# Control_Board.net
KiCad netlist of a schematic drawn in Altium Designer
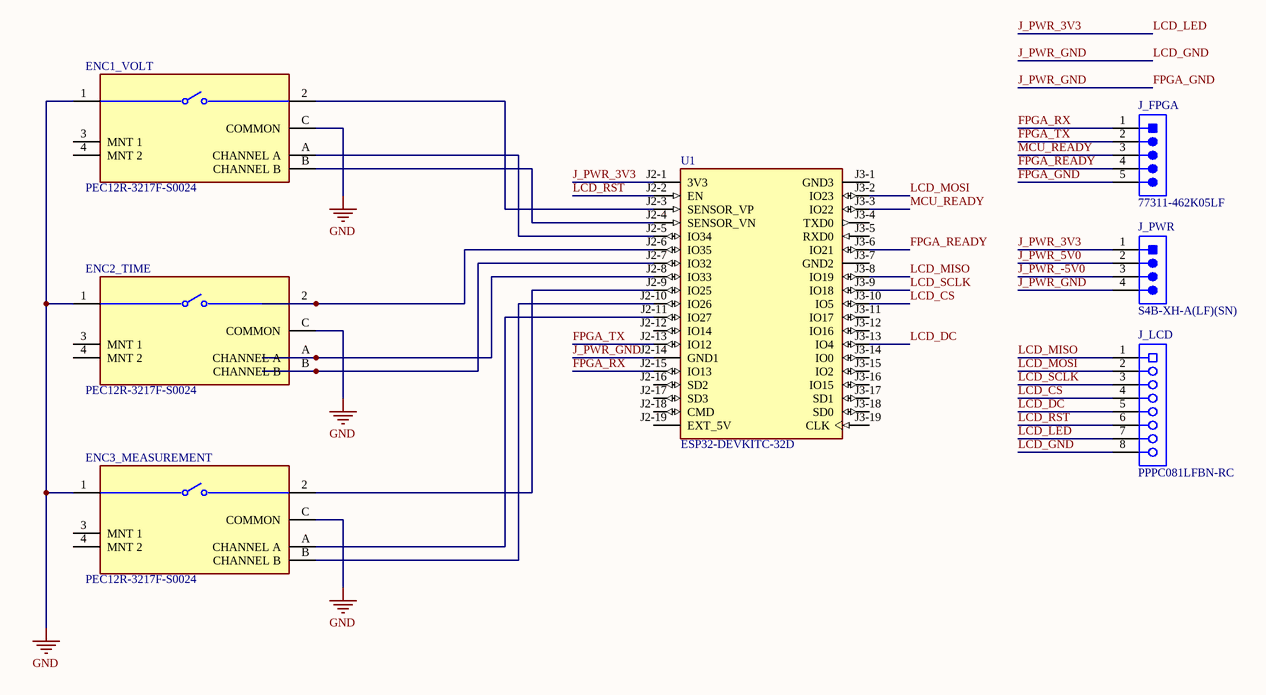
[diagram p0: Control_Board.SchDoc]

(export (version "E")
  (design (tool "Eeschema 10.0.6"))
  (components
    (comp (ref "ENC1_VOLT")
      (value "PEC12R-3217F-S0024")
      (footprint "FP-PEC12R-3217F-S0024-MFG")
      (description "ROTARY ENCODER")
      (libsource (lib "Altium Content Vault") (part "795c46dd6d7d77f565e7c060d07d204"))
    )
    (comp (ref "ENC2_TIME")
      (value "PEC12R-3217F-S0024")
      (footprint "FP-PEC12R-3217F-S0024-MFG")
      (description "ROTARY ENCODER")
      (libsource (lib "Altium Content Vault") (part "795c46dd6d7d77f565e7c060d07d204"))
    )
    (comp (ref "ENC3_MEASUREMENT")
      (value "PEC12R-3217F-S0024")
      (footprint "FP-PEC12R-3217F-S0024-MFG")
      (description "ROTARY ENCODER")
      (libsource (lib "Altium Content Vault") (part "795c46dd6d7d77f565e7c060d07d204"))
    )
    (comp (ref "J_FPGA")
      (value "77311-462K05LF")
      (footprint "FCI-77311-5_V")
      (fields (field (name "MANUFACTURER") "FCI Electronics"))
      (libsource (lib "ENEL 400") (part "CN-1P-M-R5"))
    )
    (comp (ref "J_LCD")
      (value "PPPC081LFBN-RC")
      (footprint "SLIN-PPPC081LFBN-RC_V")
      (fields (field (name "MANUFACTURER") "Sullins"))
      (libsource (lib "ENEL 400") (part "CN-1P-F-R8"))
    )
    (comp (ref "J_PWR")
      (value "S4B-XH-A(LF)(SN)")
      (footprint "JST-S4B-XH-A(LF)(SN)_V")
      (fields (field (name "MANUFACTURER") "JST"))
      (libsource (lib "ENEL 400") (part "CN-1P-M-R4"))
    )
    (comp (ref "U1")
      (value "ESP32-DEVKITC-32D")
      (footprint "MODULE_ESP32-DEVKITC-32D")
      (description "WiFi Development Tools (802.11) ESP32 General Development Kit, ESP32-WROOM-32D on the board")
      (fields (field (name "MF") "Espressif Systems"))
      (libsource (lib "ENEL 400") (part "ESP32-DEVKITC-32D"))
    )
  )
  (nets
    (net (code "1") (name "/FPGA_GND") (class "Default")
      (node (ref "J_FPGA") (pin "5") (pinfunction "CTS_5") (pintype "passive"))
      (node (ref "J_LCD") (pin "8") (pinfunction "8_8") (pintype "passive"))
      (node (ref "J_PWR") (pin "4") (pinfunction "4_4") (pintype "passive"))
      (node (ref "U1") (pin "J2-14") (pinfunction "GND1_J2-14") (pintype "power_in"))
    )
    (net (code "2") (name "/FPGA_READY") (class "Default")
      (node (ref "J_FPGA") (pin "4") (pinfunction "VCC_4") (pintype "passive"))
      (node (ref "U1") (pin "J3-6") (pinfunction "IO21_J3-6") (pintype "bidirectional"))
    )
    (net (code "3") (name "/FPGA_RX") (class "Default")
      (node (ref "J_FPGA") (pin "1") (pinfunction "DTR_1") (pintype "passive"))
      (node (ref "U1") (pin "J2-15") (pinfunction "IO13_J2-15") (pintype "bidirectional"))
    )
    (net (code "4") (name "/FPGA_TX") (class "Default")
      (node (ref "J_FPGA") (pin "2") (pinfunction "RXI_2") (pintype "passive"))
      (node (ref "U1") (pin "J2-13") (pinfunction "IO12_J2-13") (pintype "bidirectional"))
    )
    (net (code "5") (name "/J_PWR_-5V0") (class "Default")
      (node (ref "J_PWR") (pin "3") (pinfunction "3_3") (pintype "passive"))
    )
    (net (code "6") (name "/J_PWR_3V3") (class "Default")
      (node (ref "J_LCD") (pin "7") (pinfunction "7_7") (pintype "passive"))
      (node (ref "J_PWR") (pin "1") (pinfunction "1_1") (pintype "passive"))
      (node (ref "U1") (pin "J2-1") (pinfunction "3V3_J2-1") (pintype "power_in"))
    )
    (net (code "7") (name "/J_PWR_5V0") (class "Default")
      (node (ref "J_PWR") (pin "2") (pinfunction "2_2") (pintype "passive"))
    )
    (net (code "8") (name "/LCD_CS") (class "Default")
      (node (ref "J_LCD") (pin "4") (pinfunction "4_4") (pintype "passive"))
      (node (ref "U1") (pin "J3-10") (pinfunction "IO5_J3-10") (pintype "bidirectional"))
    )
    (net (code "9") (name "/LCD_DC") (class "Default")
      (node (ref "J_LCD") (pin "5") (pinfunction "5_5") (pintype "passive"))
      (node (ref "U1") (pin "J3-13") (pinfunction "IO4_J3-13") (pintype "bidirectional"))
    )
    (net (code "10") (name "/LCD_MISO") (class "Default")
      (node (ref "J_LCD") (pin "1") (pinfunction "1_1") (pintype "passive"))
      (node (ref "U1") (pin "J3-8") (pinfunction "IO19_J3-8") (pintype "bidirectional"))
    )
    (net (code "11") (name "/LCD_MOSI") (class "Default")
      (node (ref "J_LCD") (pin "2") (pinfunction "2_2") (pintype "passive"))
      (node (ref "U1") (pin "J3-2") (pinfunction "IO23_J3-2") (pintype "bidirectional"))
    )
    (net (code "12") (name "/LCD_RST") (class "Default")
      (node (ref "J_LCD") (pin "6") (pinfunction "6_6") (pintype "passive"))
      (node (ref "U1") (pin "J2-2") (pinfunction "EN_J2-2") (pintype "input"))
    )
    (net (code "13") (name "/LCD_SCLK") (class "Default")
      (node (ref "J_LCD") (pin "3") (pinfunction "3_3") (pintype "passive"))
      (node (ref "U1") (pin "J3-9") (pinfunction "IO18_J3-9") (pintype "bidirectional"))
    )
    (net (code "14") (name "/MCU_READY") (class "Default")
      (node (ref "J_FPGA") (pin "3") (pinfunction "TXO_3") (pintype "passive"))
      (node (ref "U1") (pin "J3-3") (pinfunction "IO22_J3-3") (pintype "bidirectional"))
    )
    (net (code "15") (name "GND") (class "Default")
      (node (ref "ENC1_VOLT") (pin "1") (pinfunction "1_1") (pintype "passive"))
      (node (ref "ENC1_VOLT") (pin "C") (pinfunction "COMMON_C") (pintype "passive"))
      (node (ref "ENC2_TIME") (pin "1") (pinfunction "1_1") (pintype "passive"))
      (node (ref "ENC2_TIME") (pin "C") (pinfunction "COMMON_C") (pintype "passive"))
      (node (ref "ENC3_MEASUREMENT") (pin "1") (pinfunction "1_1") (pintype "passive"))
      (node (ref "ENC3_MEASUREMENT") (pin "C") (pinfunction "COMMON_C") (pintype "passive"))
    )
    (net (code "16") (name "Net-(ENC1_VOLT-CHANNEL_A)") (class "Default")
      (node (ref "ENC1_VOLT") (pin "A") (pinfunction "CHANNEL_A_A") (pintype "passive"))
      (node (ref "U1") (pin "J2-5") (pinfunction "IO34_J2-5") (pintype "bidirectional"))
    )
    (net (code "17") (name "Net-(ENC1_VOLT-CHANNEL_B)") (class "Default")
      (node (ref "ENC1_VOLT") (pin "B") (pinfunction "CHANNEL_B_B") (pintype "passive"))
      (node (ref "U1") (pin "J2-4") (pinfunction "SENSOR_VN_J2-4") (pintype "input"))
    )
    (net (code "18") (name "Net-(ENC2_TIME-CHANNEL_A)") (class "Default")
      (node (ref "ENC2_TIME") (pin "A") (pinfunction "CHANNEL_A_A") (pintype "passive"))
      (node (ref "U1") (pin "J2-8") (pinfunction "IO33_J2-8") (pintype "bidirectional"))
    )
    (net (code "19") (name "Net-(ENC2_TIME-CHANNEL_B)") (class "Default")
      (node (ref "ENC2_TIME") (pin "B") (pinfunction "CHANNEL_B_B") (pintype "passive"))
      (node (ref "U1") (pin "J2-7") (pinfunction "IO32_J2-7") (pintype "bidirectional"))
    )
    (net (code "20") (name "Net-(ENC3_MEASUREMENT-CHANNEL_A)") (class "Default")
      (node (ref "ENC3_MEASUREMENT") (pin "A") (pinfunction "CHANNEL_A_A") (pintype "passive"))
      (node (ref "U1") (pin "J2-11") (pinfunction "IO27_J2-11") (pintype "bidirectional"))
    )
    (net (code "21") (name "Net-(ENC3_MEASUREMENT-CHANNEL_B)") (class "Default")
      (node (ref "ENC3_MEASUREMENT") (pin "B") (pinfunction "CHANNEL_B_B") (pintype "passive"))
      (node (ref "U1") (pin "J2-10") (pinfunction "IO26_J2-10") (pintype "bidirectional"))
    )
    (net (code "22") (name "Net-(U1-IO25)") (class "Default")
      (node (ref "ENC3_MEASUREMENT") (pin "2") (pinfunction "2_2") (pintype "passive"))
      (node (ref "U1") (pin "J2-9") (pinfunction "IO25_J2-9") (pintype "bidirectional"))
    )
    (net (code "23") (name "Net-(U1-IO35)") (class "Default")
      (node (ref "ENC2_TIME") (pin "2") (pinfunction "2_2") (pintype "passive"))
      (node (ref "U1") (pin "J2-6") (pinfunction "IO35_J2-6") (pintype "bidirectional"))
    )
    (net (code "24") (name "Net-(U1-SENSOR_VP)") (class "Default")
      (node (ref "ENC1_VOLT") (pin "2") (pinfunction "2_2") (pintype "passive"))
      (node (ref "U1") (pin "J2-3") (pinfunction "SENSOR_VP_J2-3") (pintype "input"))
    )
    (net (code "25") (name "unconnected-(ENC1_VOLT-MNT_1-Pad3)") (class "Default")
      (node (ref "ENC1_VOLT") (pin "3") (pinfunction "MNT_1_3") (pintype "passive"))
    )
    (net (code "26") (name "unconnected-(ENC1_VOLT-MNT_2-Pad4)") (class "Default")
      (node (ref "ENC1_VOLT") (pin "4") (pinfunction "MNT_2_4") (pintype "passive"))
    )
    (net (code "27") (name "unconnected-(ENC2_TIME-MNT_1-Pad3)") (class "Default")
      (node (ref "ENC2_TIME") (pin "3") (pinfunction "MNT_1_3") (pintype "passive"))
    )
    (net (code "28") (name "unconnected-(ENC2_TIME-MNT_2-Pad4)") (class "Default")
      (node (ref "ENC2_TIME") (pin "4") (pinfunction "MNT_2_4") (pintype "passive"))
    )
    (net (code "29") (name "unconnected-(ENC3_MEASUREMENT-MNT_1-Pad3)") (class "Default")
      (node (ref "ENC3_MEASUREMENT") (pin "3") (pinfunction "MNT_1_3") (pintype "passive"))
    )
    (net (code "30") (name "unconnected-(ENC3_MEASUREMENT-MNT_2-Pad4)") (class "Default")
      (node (ref "ENC3_MEASUREMENT") (pin "4") (pinfunction "MNT_2_4") (pintype "passive"))
    )
    (net (code "31") (name "unconnected-(U1-CLK-PadJ3-19)") (class "Default")
      (node (ref "U1") (pin "J3-19") (pinfunction "CLK_J3-19") (pintype "input"))
    )
    (net (code "32") (name "unconnected-(U1-CMD-PadJ2-18)") (class "Default")
      (node (ref "U1") (pin "J2-18") (pinfunction "CMD_J2-18") (pintype "bidirectional"))
    )
    (net (code "33") (name "unconnected-(U1-EXT_5V-PadJ2-19)") (class "Default")
      (node (ref "U1") (pin "J2-19") (pinfunction "EXT_5V_J2-19") (pintype "power_in"))
    )
    (net (code "34") (name "unconnected-(U1-GND2-PadJ3-7)") (class "Default")
      (node (ref "U1") (pin "J3-7") (pinfunction "GND2_J3-7") (pintype "power_in"))
    )
    (net (code "35") (name "unconnected-(U1-GND3-PadJ3-1)") (class "Default")
      (node (ref "U1") (pin "J3-1") (pinfunction "GND3_J3-1") (pintype "power_in"))
    )
    (net (code "36") (name "unconnected-(U1-IO0-PadJ3-14)") (class "Default")
      (node (ref "U1") (pin "J3-14") (pinfunction "IO0_J3-14") (pintype "bidirectional"))
    )
    (net (code "37") (name "unconnected-(U1-IO2-PadJ3-15)") (class "Default")
      (node (ref "U1") (pin "J3-15") (pinfunction "IO2_J3-15") (pintype "bidirectional"))
    )
    (net (code "38") (name "unconnected-(U1-IO14-PadJ2-12)") (class "Default")
      (node (ref "U1") (pin "J2-12") (pinfunction "IO14_J2-12") (pintype "bidirectional"))
    )
    (net (code "39") (name "unconnected-(U1-IO15-PadJ3-16)") (class "Default")
      (node (ref "U1") (pin "J3-16") (pinfunction "IO15_J3-16") (pintype "bidirectional"))
    )
    (net (code "40") (name "unconnected-(U1-IO16-PadJ3-12)") (class "Default")
      (node (ref "U1") (pin "J3-12") (pinfunction "IO16_J3-12") (pintype "bidirectional"))
    )
    (net (code "41") (name "unconnected-(U1-IO17-PadJ3-11)") (class "Default")
      (node (ref "U1") (pin "J3-11") (pinfunction "IO17_J3-11") (pintype "bidirectional"))
    )
    (net (code "42") (name "unconnected-(U1-RXD0-PadJ3-5)") (class "Default")
      (node (ref "U1") (pin "J3-5") (pinfunction "RXD0_J3-5") (pintype "input"))
    )
    (net (code "43") (name "unconnected-(U1-SD0-PadJ3-18)") (class "Default")
      (node (ref "U1") (pin "J3-18") (pinfunction "SD0_J3-18") (pintype "bidirectional"))
    )
    (net (code "44") (name "unconnected-(U1-SD1-PadJ3-17)") (class "Default")
      (node (ref "U1") (pin "J3-17") (pinfunction "SD1_J3-17") (pintype "bidirectional"))
    )
    (net (code "45") (name "unconnected-(U1-SD2-PadJ2-16)") (class "Default")
      (node (ref "U1") (pin "J2-16") (pinfunction "SD2_J2-16") (pintype "bidirectional"))
    )
    (net (code "46") (name "unconnected-(U1-SD3-PadJ2-17)") (class "Default")
      (node (ref "U1") (pin "J2-17") (pinfunction "SD3_J2-17") (pintype "bidirectional"))
    )
    (net (code "47") (name "unconnected-(U1-TXD0-PadJ3-4)") (class "Default")
      (node (ref "U1") (pin "J3-4") (pinfunction "TXD0_J3-4") (pintype "output"))
    )
  )
)
